# Project_Czepil_Zwolinska_1.net
KiCad netlist of a schematic drawn in EAGLE
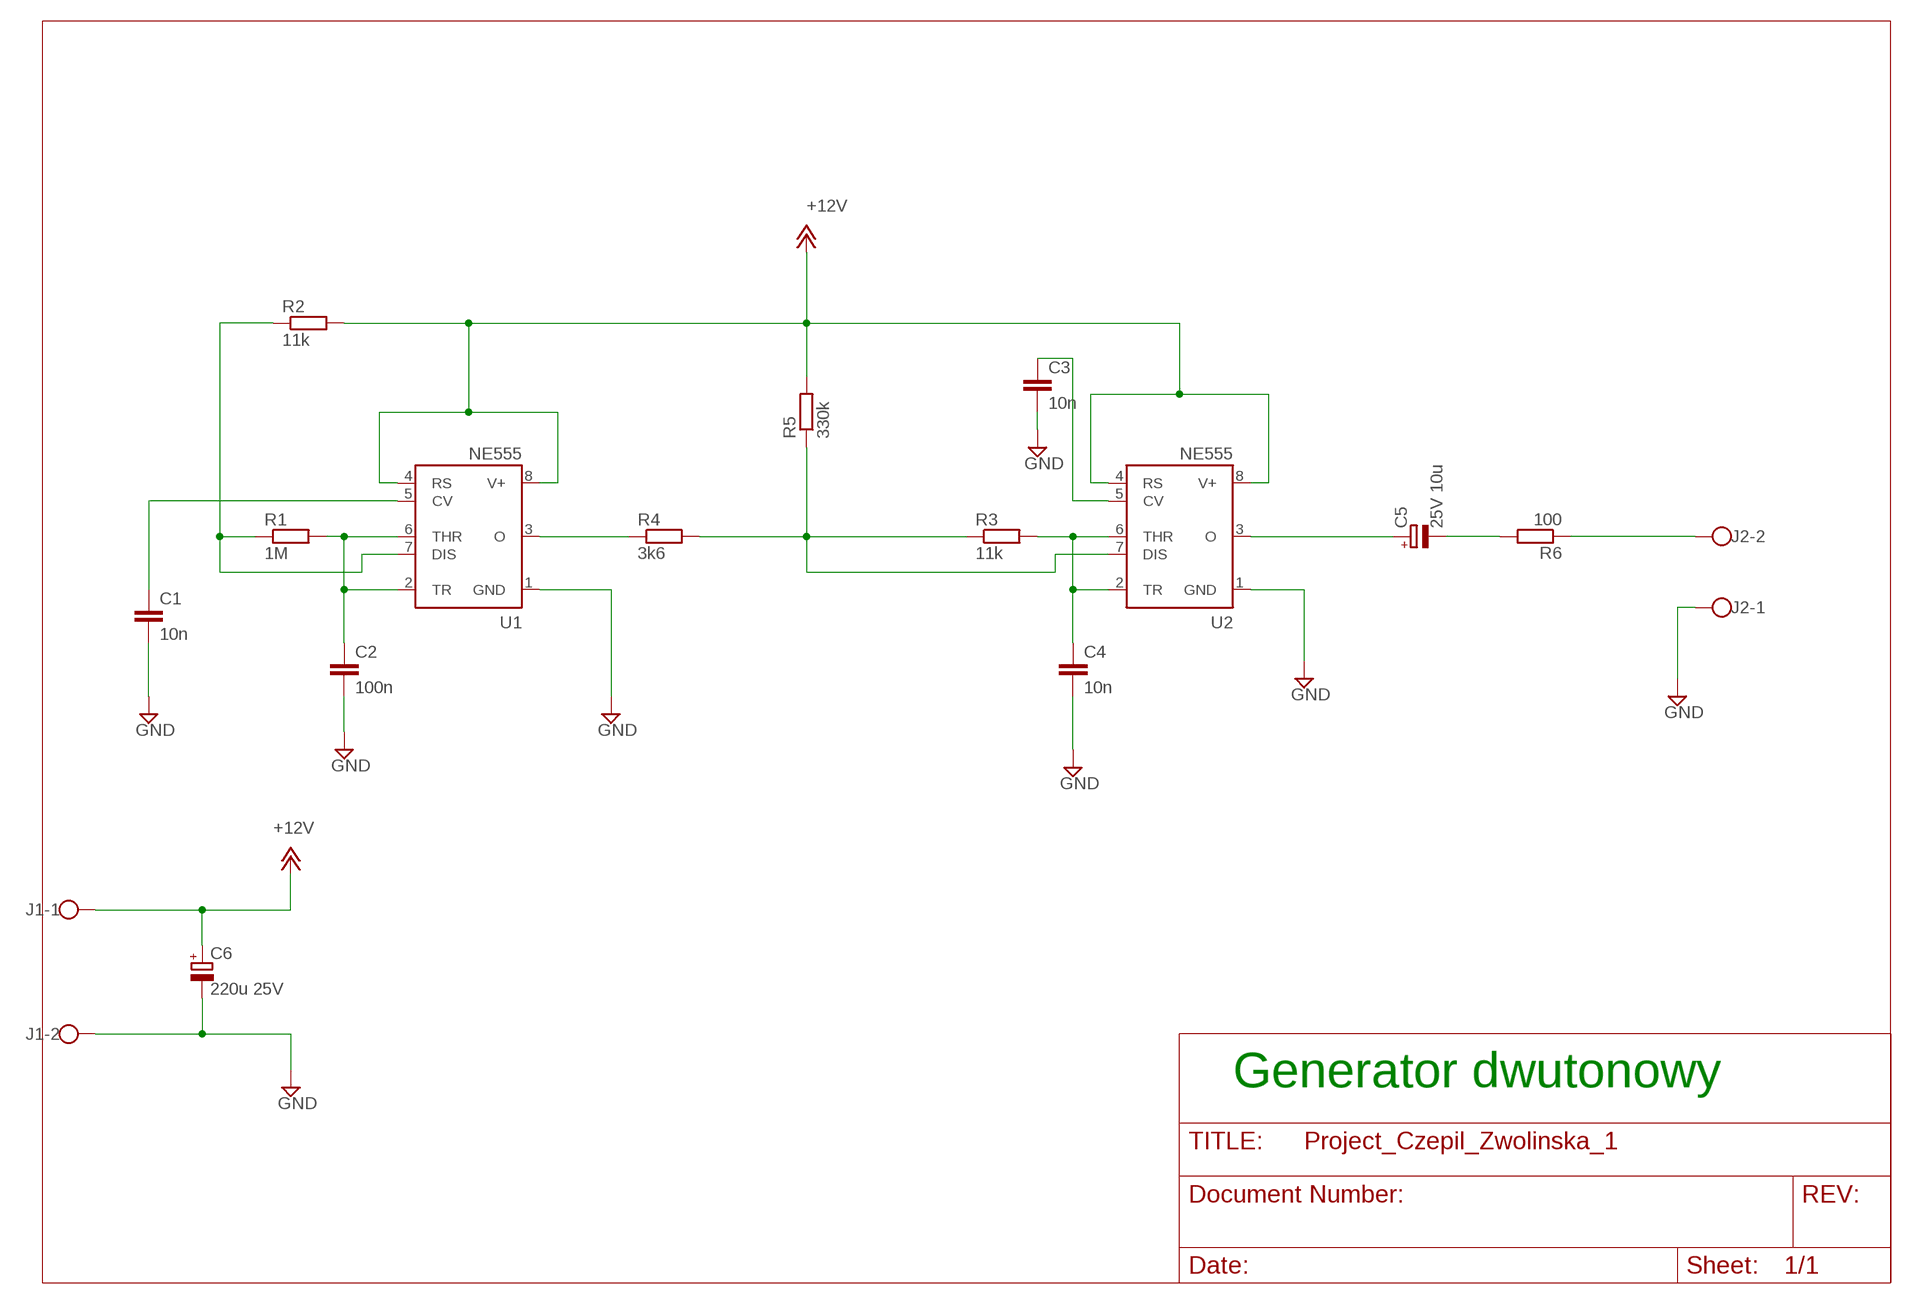
[diagram p0: schematic, sheet 1]

(export (version "E")
  (design (tool "Eeschema 10.0.6"))
  (components
    (comp (ref "C1")
      (value "10n")
      (footprint "eagle-import:C1206")
      (libsource (lib "eagle-import") (part "C-EUC1206"))
    )
    (comp (ref "C2")
      (value "100n")
      (footprint "eagle-import:C1206")
      (libsource (lib "eagle-import") (part "C-EUC1206"))
    )
    (comp (ref "C3")
      (value "10n")
      (footprint "eagle-import:C1206")
      (libsource (lib "eagle-import") (part "C-EUC1206"))
    )
    (comp (ref "C4")
      (value "10n")
      (footprint "eagle-import:C1206")
      (libsource (lib "eagle-import") (part "C-EUC1206"))
    )
    (comp (ref "C5")
      (value "25V 10u")
      (footprint "eagle-import:E1,8-4")
      (libsource (lib "eagle-import") (part "CPOL-EUE1.8-4"))
    )
    (comp (ref "C6")
      (value "220u 25V")
      (footprint "eagle-import:E2-4")
      (libsource (lib "eagle-import") (part "CPOL-EUE2-4"))
    )
    (comp (ref "J1")
      (value "W237-102")
      (footprint "eagle-import:W237-102")
      (fields (field (name "MPN") "237-102"))
      (libsource (lib "eagle-import") (part "W237-102"))
    )
    (comp (ref "J2")
      (value "W237-102")
      (footprint "eagle-import:W237-102")
      (fields (field (name "MPN") "237-102"))
      (libsource (lib "eagle-import") (part "W237-102"))
    )
    (comp (ref "R1")
      (value "1M")
      (footprint "eagle-import:0207_10")
      (libsource (lib "eagle-import") (part "R-EU_0207/10"))
    )
    (comp (ref "R2")
      (value "11k")
      (footprint "eagle-import:0207_10")
      (libsource (lib "eagle-import") (part "R-EU_0207/10"))
    )
    (comp (ref "R3")
      (value "11k")
      (footprint "eagle-import:0207_10")
      (libsource (lib "eagle-import") (part "R-EU_0207/10"))
    )
    (comp (ref "R4")
      (value "3k6")
      (footprint "eagle-import:0207_10")
      (libsource (lib "eagle-import") (part "R-EU_0207/10"))
    )
    (comp (ref "R5")
      (value "330k")
      (footprint "eagle-import:0207_10")
      (libsource (lib "eagle-import") (part "R-EU_0207/10"))
    )
    (comp (ref "R6")
      (value "100")
      (footprint "eagle-import:0207_10")
      (libsource (lib "eagle-import") (part "R-EU_0207/10"))
    )
    (comp (ref "U1")
      (value "NE555")
      (footprint "eagle-import:DIL-08")
      (fields (field (name "MF") "Arrow Electronics") (field (name "MPN") "NE555N"))
      (libsource (lib "eagle-import") (part "NE555"))
    )
    (comp (ref "U2")
      (value "NE555")
      (footprint "eagle-import:DIL-08")
      (fields (field (name "MF") "Arrow Electronics") (field (name "MPN") "NE555N"))
      (libsource (lib "eagle-import") (part "NE555"))
    )
  )
  (nets
    (net (code "1") (name "+12V") (class "Default")
      (node (ref "C6") (pin "+") (pinfunction "+_+") (pintype "passive"))
      (node (ref "J1") (pin "1") (pinfunction "KL_1") (pintype "passive"))
      (node (ref "R2") (pin "2") (pinfunction "2_2") (pintype "passive"))
      (node (ref "R5") (pin "2") (pinfunction "2_2") (pintype "passive"))
      (node (ref "U1") (pin "4") (pinfunction "RS_4") (pintype "input"))
      (node (ref "U1") (pin "8") (pinfunction "V+_8") (pintype "power_in"))
      (node (ref "U2") (pin "4") (pinfunction "RS_4") (pintype "input"))
      (node (ref "U2") (pin "8") (pinfunction "V+_8") (pintype "power_in"))
    )
    (net (code "2") (name "GND") (class "Default")
      (node (ref "C1") (pin "2") (pinfunction "2_2") (pintype "passive"))
      (node (ref "C2") (pin "2") (pinfunction "2_2") (pintype "passive"))
      (node (ref "C3") (pin "2") (pinfunction "2_2") (pintype "passive"))
      (node (ref "C4") (pin "2") (pinfunction "2_2") (pintype "passive"))
      (node (ref "C6") (pin "-") (pinfunction "-_-") (pintype "passive"))
      (node (ref "J1") (pin "2") (pinfunction "KL_2") (pintype "passive"))
      (node (ref "J2") (pin "1") (pinfunction "KL_1") (pintype "passive"))
      (node (ref "U1") (pin "1") (pinfunction "GND_1") (pintype "power_in"))
      (node (ref "U2") (pin "1") (pinfunction "GND_1") (pintype "power_in"))
    )
    (net (code "3") (name "Net-(C5-Pad-)") (class "Default")
      (node (ref "C5") (pin "-") (pinfunction "-_-") (pintype "passive"))
      (node (ref "R6") (pin "2") (pinfunction "2_2") (pintype "passive"))
    )
    (net (code "4") (name "Net-(J2B-KL)") (class "Default")
      (node (ref "J2") (pin "2") (pinfunction "KL_2") (pintype "passive"))
      (node (ref "R6") (pin "1") (pinfunction "1_1") (pintype "passive"))
    )
    (net (code "5") (name "Net-(U1-CV)") (class "Default")
      (node (ref "C1") (pin "1") (pinfunction "1_1") (pintype "passive"))
      (node (ref "U1") (pin "5") (pinfunction "CV_5") (pintype "input"))
    )
    (net (code "6") (name "Net-(U1-DIS)") (class "Default")
      (node (ref "R1") (pin "1") (pinfunction "1_1") (pintype "passive"))
      (node (ref "R2") (pin "1") (pinfunction "1_1") (pintype "passive"))
      (node (ref "U1") (pin "7") (pinfunction "DIS_7") (pintype "input"))
    )
    (net (code "7") (name "Net-(U1-O)") (class "Default")
      (node (ref "R4") (pin "1") (pinfunction "1_1") (pintype "passive"))
      (node (ref "U1") (pin "3") (pinfunction "O_3") (pintype "output"))
    )
    (net (code "8") (name "Net-(U1-THR)") (class "Default")
      (node (ref "C2") (pin "1") (pinfunction "1_1") (pintype "passive"))
      (node (ref "R1") (pin "2") (pinfunction "2_2") (pintype "passive"))
      (node (ref "U1") (pin "2") (pinfunction "TR_2") (pintype "input"))
      (node (ref "U1") (pin "6") (pinfunction "THR_6") (pintype "input"))
    )
    (net (code "9") (name "Net-(U2-CV)") (class "Default")
      (node (ref "C3") (pin "1") (pinfunction "1_1") (pintype "passive"))
      (node (ref "U2") (pin "5") (pinfunction "CV_5") (pintype "input"))
    )
    (net (code "10") (name "Net-(U2-DIS)") (class "Default")
      (node (ref "R3") (pin "1") (pinfunction "1_1") (pintype "passive"))
      (node (ref "R4") (pin "2") (pinfunction "2_2") (pintype "passive"))
      (node (ref "R5") (pin "1") (pinfunction "1_1") (pintype "passive"))
      (node (ref "U2") (pin "7") (pinfunction "DIS_7") (pintype "input"))
    )
    (net (code "11") (name "Net-(U2-O)") (class "Default")
      (node (ref "C5") (pin "+") (pinfunction "+_+") (pintype "passive"))
      (node (ref "U2") (pin "3") (pinfunction "O_3") (pintype "output"))
    )
    (net (code "12") (name "Net-(U2-THR)") (class "Default")
      (node (ref "C4") (pin "1") (pinfunction "1_1") (pintype "passive"))
      (node (ref "R3") (pin "2") (pinfunction "2_2") (pintype "passive"))
      (node (ref "U2") (pin "2") (pinfunction "TR_2") (pintype "input"))
      (node (ref "U2") (pin "6") (pinfunction "THR_6") (pintype "input"))
    )
  )
)
